# MYC_Homematic.net
KiCad netlist of a schematic drawn in EAGLE
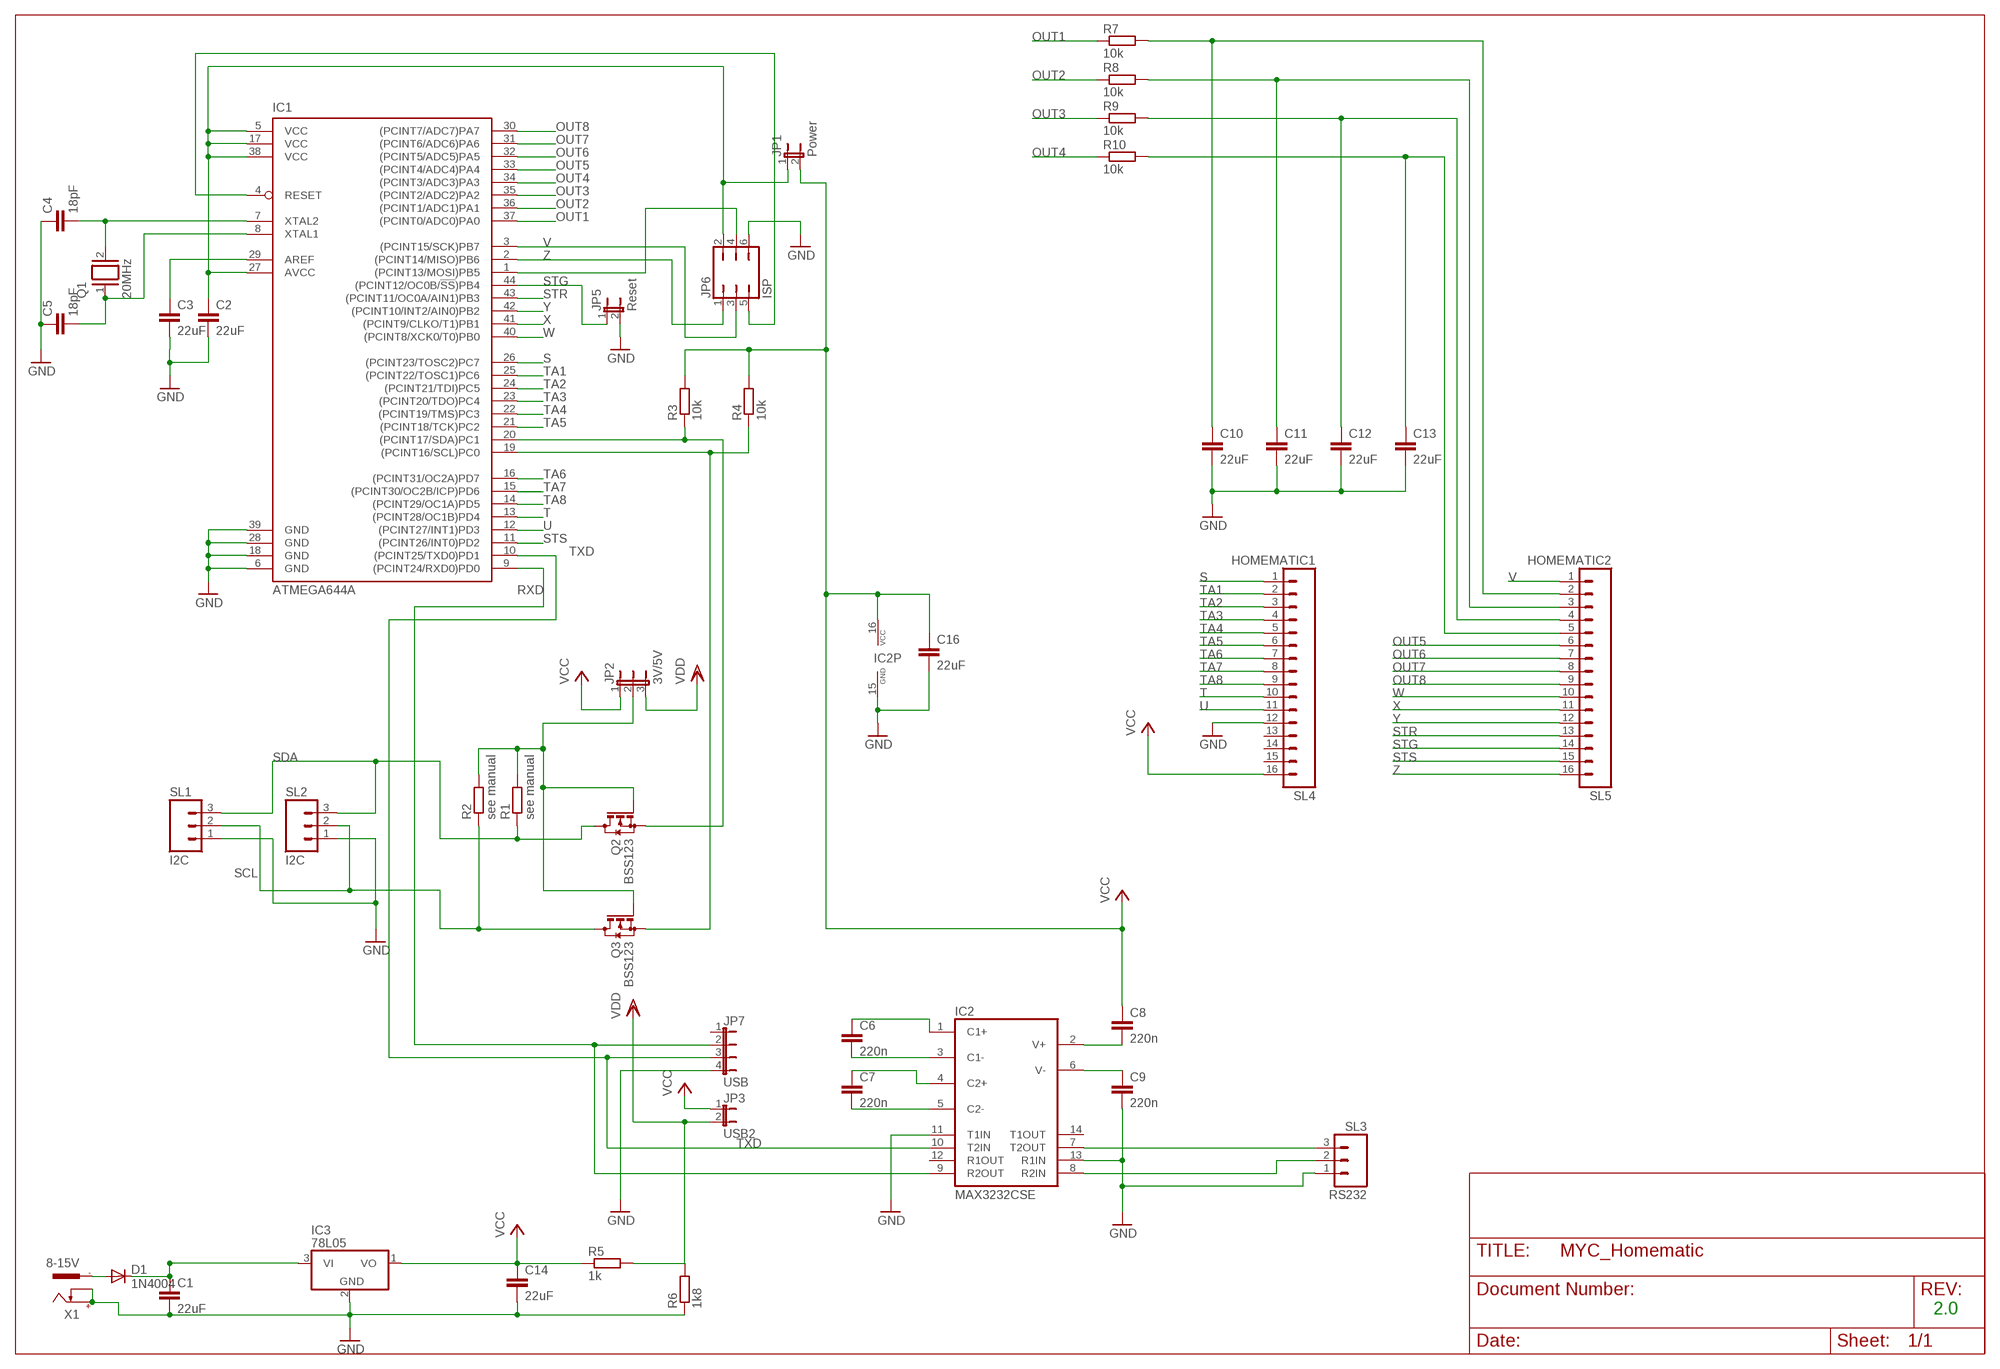
[diagram p0: schematic, sheet 1]

(export (version "E")
  (design (tool "Eeschema 10.0.6"))
  (components
    (comp (ref "C1")
      (value "22uF")
      (footprint "eagle-import:C1206")
      (libsource (lib "eagle-import") (part "C-EUC1206"))
    )
    (comp (ref "C2")
      (value "22uF")
      (footprint "eagle-import:C1206")
      (libsource (lib "eagle-import") (part "C-EUC1206"))
    )
    (comp (ref "C3")
      (value "22uF")
      (footprint "eagle-import:C1206")
      (libsource (lib "eagle-import") (part "C-EUC1206"))
    )
    (comp (ref "C4")
      (value "18pF")
      (footprint "eagle-import:C025-030X050")
      (libsource (lib "eagle-import") (part "C-EU025-030X050"))
    )
    (comp (ref "C5")
      (value "18pF")
      (footprint "eagle-import:C025-030X050")
      (libsource (lib "eagle-import") (part "C-EU025-030X050"))
    )
    (comp (ref "C6")
      (value "220n")
      (footprint "eagle-import:C1206")
      (libsource (lib "eagle-import") (part "C-EUC1206"))
    )
    (comp (ref "C7")
      (value "220n")
      (footprint "eagle-import:C1206")
      (libsource (lib "eagle-import") (part "C-EUC1206"))
    )
    (comp (ref "C8")
      (value "220n")
      (footprint "eagle-import:C1206")
      (libsource (lib "eagle-import") (part "C-EUC1206"))
    )
    (comp (ref "C9")
      (value "220n")
      (footprint "eagle-import:C1206")
      (libsource (lib "eagle-import") (part "C-EUC1206"))
    )
    (comp (ref "C10")
      (value "22uF")
      (footprint "eagle-import:C1206")
      (libsource (lib "eagle-import") (part "C-EUC1206"))
    )
    (comp (ref "C11")
      (value "22uF")
      (footprint "eagle-import:C1206")
      (libsource (lib "eagle-import") (part "C-EUC1206"))
    )
    (comp (ref "C12")
      (value "22uF")
      (footprint "eagle-import:C1206")
      (libsource (lib "eagle-import") (part "C-EUC1206"))
    )
    (comp (ref "C13")
      (value "22uF")
      (footprint "eagle-import:C1206")
      (libsource (lib "eagle-import") (part "C-EUC1206"))
    )
    (comp (ref "C14")
      (value "22uF")
      (footprint "eagle-import:C1206")
      (libsource (lib "eagle-import") (part "C-EUC1206"))
    )
    (comp (ref "C16")
      (value "22uF")
      (footprint "eagle-import:C1206")
      (libsource (lib "eagle-import") (part "C-EUC1206"))
    )
    (comp (ref "D1")
      (value "1N4004")
      (footprint "eagle-import:DO41-10")
      (libsource (lib "eagle-import") (part "1N4004"))
    )
    (comp (ref "IC1")
      (value "ATMEGA644A")
      (footprint "eagle-import:TQFP44")
      (fields (field (name "MPN") "ATMEGA644PV-10AU"))
      (libsource (lib "eagle-import") (part "ATMEGA644A"))
    )
    (comp (ref "IC2")
      (value "MAX3232CSE")
      (footprint "eagle-import:SO16")
      (libsource (lib "eagle-import") (part "MAX3232SEC"))
    )
    (comp (ref "IC3")
      (value "78L05")
      (footprint "eagle-import:TO92")
      (libsource (lib "eagle-import") (part "78L05"))
    )
    (comp (ref "JP1")
      (value "Power")
      (footprint "eagle-import:JP1")
      (libsource (lib "eagle-import") (part "JP1E"))
    )
    (comp (ref "JP2")
      (value "3V/5V")
      (footprint "eagle-import:JP2")
      (libsource (lib "eagle-import") (part "JP2E"))
    )
    (comp (ref "JP3")
      (value "USB2")
      (footprint "eagle-import:JP1")
      (libsource (lib "eagle-import") (part "JP1E"))
    )
    (comp (ref "JP5")
      (value "Reset")
      (footprint "eagle-import:JP1")
      (libsource (lib "eagle-import") (part "JP1E"))
    )
    (comp (ref "JP6")
      (value "ISP")
      (footprint "eagle-import:JP3Q")
      (libsource (lib "eagle-import") (part "JP3Q"))
    )
    (comp (ref "JP7")
      (value "USB")
      (footprint "eagle-import:JP4")
      (libsource (lib "eagle-import") (part "JP4E"))
    )
    (comp (ref "Q1")
      (value "20MHz")
      (footprint "eagle-import:QS")
      (libsource (lib "eagle-import") (part "XTAL/S"))
    )
    (comp (ref "Q2")
      (value "BSS123")
      (footprint "eagle-import:SOT23")
      (libsource (lib "eagle-import") (part "BSS123"))
    )
    (comp (ref "Q3")
      (value "BSS123")
      (footprint "eagle-import:SOT23")
      (libsource (lib "eagle-import") (part "BSS123"))
    )
    (comp (ref "R1")
      (value "see manual")
      (footprint "eagle-import:R1206")
      (libsource (lib "eagle-import") (part "R-EU_R1206"))
    )
    (comp (ref "R2")
      (value "see manual")
      (footprint "eagle-import:R1206")
      (libsource (lib "eagle-import") (part "R-EU_R1206"))
    )
    (comp (ref "R3")
      (value "10k")
      (footprint "eagle-import:R1206")
      (libsource (lib "eagle-import") (part "R-EU_R1206"))
    )
    (comp (ref "R4")
      (value "10k")
      (footprint "eagle-import:R1206")
      (libsource (lib "eagle-import") (part "R-EU_R1206"))
    )
    (comp (ref "R5")
      (value "1k")
      (footprint "eagle-import:R1206")
      (libsource (lib "eagle-import") (part "R-EU_R1206"))
    )
    (comp (ref "R6")
      (value "1k8")
      (footprint "eagle-import:R1206")
      (libsource (lib "eagle-import") (part "R-EU_R1206"))
    )
    (comp (ref "R7")
      (value "10k")
      (footprint "eagle-import:R1206")
      (libsource (lib "eagle-import") (part "R-EU_R1206"))
    )
    (comp (ref "R8")
      (value "10k")
      (footprint "eagle-import:R1206")
      (libsource (lib "eagle-import") (part "R-EU_R1206"))
    )
    (comp (ref "R9")
      (value "10k")
      (footprint "eagle-import:R1206")
      (libsource (lib "eagle-import") (part "R-EU_R1206"))
    )
    (comp (ref "R10")
      (value "10k")
      (footprint "eagle-import:R1206")
      (libsource (lib "eagle-import") (part "R-EU_R1206"))
    )
    (comp (ref "SL1")
      (value "I2C")
      (footprint "eagle-import:03P")
      (libsource (lib "eagle-import") (part "M03"))
    )
    (comp (ref "SL2")
      (value "I2C")
      (footprint "eagle-import:03P")
      (libsource (lib "eagle-import") (part "M03"))
    )
    (comp (ref "SL3")
      (value "RS232")
      (footprint "eagle-import:03P")
      (libsource (lib "eagle-import") (part "M03"))
    )
    (comp (ref "SL4")
      (value "HOMEMATIC1")
      (footprint "eagle-import:16P")
      (libsource (lib "eagle-import") (part "M16"))
    )
    (comp (ref "SL5")
      (value "HOMEMATIC2")
      (footprint "eagle-import:16P")
      (libsource (lib "eagle-import") (part "M16"))
    )
    (comp (ref "X1")
      (value "8-15V")
      (footprint "eagle-import:737992-5")
      (libsource (lib "eagle-import") (part "737992-55"))
    )
  )
  (nets
    (net (code "1") (name "/OUT1") (class "Default")
      (node (ref "IC1") (pin "37") (pinfunction "(PCINT0/ADC0)PA0_37") (pintype "bidirectional"))
      (node (ref "R7") (pin "1") (pinfunction "1_1") (pintype "passive"))
    )
    (net (code "2") (name "/OUT2") (class "Default")
      (node (ref "IC1") (pin "36") (pinfunction "(PCINT1/ADC1)PA1_36") (pintype "bidirectional"))
      (node (ref "R8") (pin "1") (pinfunction "1_1") (pintype "passive"))
    )
    (net (code "3") (name "/OUT3") (class "Default")
      (node (ref "IC1") (pin "35") (pinfunction "(PCINT2/ADC2)PA2_35") (pintype "bidirectional"))
      (node (ref "R9") (pin "1") (pinfunction "1_1") (pintype "passive"))
    )
    (net (code "4") (name "/OUT4") (class "Default")
      (node (ref "IC1") (pin "34") (pinfunction "(PCINT3/ADC3)PA3_34") (pintype "bidirectional"))
      (node (ref "R10") (pin "1") (pinfunction "1_1") (pintype "passive"))
    )
    (net (code "5") (name "/OUT5") (class "Default")
      (node (ref "IC1") (pin "33") (pinfunction "(PCINT4/ADC4)PA4_33") (pintype "bidirectional"))
      (node (ref "SL5") (pin "6") (pinfunction "6_6") (pintype "passive"))
    )
    (net (code "6") (name "/OUT6") (class "Default")
      (node (ref "IC1") (pin "32") (pinfunction "(PCINT5/ADC5)PA5_32") (pintype "bidirectional"))
      (node (ref "SL5") (pin "7") (pinfunction "7_7") (pintype "passive"))
    )
    (net (code "7") (name "/OUT7") (class "Default")
      (node (ref "IC1") (pin "31") (pinfunction "(PCINT6/ADC6)PA6_31") (pintype "bidirectional"))
      (node (ref "SL5") (pin "8") (pinfunction "8_8") (pintype "passive"))
    )
    (net (code "8") (name "/OUT8") (class "Default")
      (node (ref "IC1") (pin "30") (pinfunction "(PCINT7/ADC7)PA7_30") (pintype "bidirectional"))
      (node (ref "SL5") (pin "9") (pinfunction "9_9") (pintype "passive"))
    )
    (net (code "9") (name "/RXD") (class "Default")
      (node (ref "IC1") (pin "9") (pinfunction "(PCINT24/RXD0)PD0_9") (pintype "bidirectional"))
      (node (ref "IC2") (pin "9") (pinfunction "R2OUT_9") (pintype "output"))
      (node (ref "JP7") (pin "2") (pinfunction "2_2") (pintype "passive"))
    )
    (net (code "10") (name "/S") (class "Default")
      (node (ref "IC1") (pin "26") (pinfunction "(PCINT23/TOSC2)PC7_26") (pintype "output"))
      (node (ref "SL4") (pin "1") (pinfunction "1_1") (pintype "passive"))
    )
    (net (code "11") (name "/SCL") (class "Default")
      (node (ref "Q3") (pin "3") (pinfunction "D_3") (pintype "passive"))
      (node (ref "R2") (pin "1") (pinfunction "1_1") (pintype "passive"))
      (node (ref "SL1") (pin "2") (pinfunction "2_2") (pintype "passive"))
      (node (ref "SL2") (pin "2") (pinfunction "2_2") (pintype "passive"))
    )
    (net (code "12") (name "/SDA") (class "Default")
      (node (ref "Q2") (pin "3") (pinfunction "D_3") (pintype "passive"))
      (node (ref "R1") (pin "1") (pinfunction "1_1") (pintype "passive"))
      (node (ref "SL1") (pin "3") (pinfunction "3_3") (pintype "passive"))
      (node (ref "SL2") (pin "3") (pinfunction "3_3") (pintype "passive"))
    )
    (net (code "13") (name "/STG") (class "Default")
      (node (ref "IC1") (pin "44") (pinfunction "(PCINT12/OC0B/~{SS})PB4_44") (pintype "bidirectional"))
      (node (ref "JP5") (pin "1") (pinfunction "1_1") (pintype "passive"))
      (node (ref "SL5") (pin "14") (pinfunction "14_14") (pintype "passive"))
    )
    (net (code "14") (name "/STR") (class "Default")
      (node (ref "IC1") (pin "43") (pinfunction "(PCINT11/OC0A/AIN1)PB3_43") (pintype "bidirectional"))
      (node (ref "SL5") (pin "13") (pinfunction "13_13") (pintype "passive"))
    )
    (net (code "15") (name "/STS") (class "Default")
      (node (ref "IC1") (pin "11") (pinfunction "(PCINT26/INT0)PD2_11") (pintype "bidirectional"))
      (node (ref "SL5") (pin "15") (pinfunction "15_15") (pintype "passive"))
    )
    (net (code "16") (name "/T") (class "Default")
      (node (ref "IC1") (pin "13") (pinfunction "(PCINT28/OC1B)PD4_13") (pintype "bidirectional"))
      (node (ref "SL4") (pin "10") (pinfunction "10_10") (pintype "passive"))
    )
    (net (code "17") (name "/TA1") (class "Default")
      (node (ref "IC1") (pin "25") (pinfunction "(PCINT22/TOSC1)PC6_25") (pintype "output"))
      (node (ref "SL4") (pin "2") (pinfunction "2_2") (pintype "passive"))
    )
    (net (code "18") (name "/TA2") (class "Default")
      (node (ref "IC1") (pin "24") (pinfunction "(PCINT21/TDI)PC5_24") (pintype "output"))
      (node (ref "SL4") (pin "3") (pinfunction "3_3") (pintype "passive"))
    )
    (net (code "19") (name "/TA3") (class "Default")
      (node (ref "IC1") (pin "23") (pinfunction "(PCINT20/TDO)PC4_23") (pintype "output"))
      (node (ref "SL4") (pin "4") (pinfunction "4_4") (pintype "passive"))
    )
    (net (code "20") (name "/TA4") (class "Default")
      (node (ref "IC1") (pin "22") (pinfunction "(PCINT19/TMS)PC3_22") (pintype "output"))
      (node (ref "SL4") (pin "5") (pinfunction "5_5") (pintype "passive"))
    )
    (net (code "21") (name "/TA5") (class "Default")
      (node (ref "IC1") (pin "21") (pinfunction "(PCINT18/TCK)PC2_21") (pintype "output"))
      (node (ref "SL4") (pin "6") (pinfunction "6_6") (pintype "passive"))
    )
    (net (code "22") (name "/TA6") (class "Default")
      (node (ref "IC1") (pin "16") (pinfunction "(PCINT31/OC2A)PD7_16") (pintype "bidirectional"))
      (node (ref "SL4") (pin "7") (pinfunction "7_7") (pintype "passive"))
    )
    (net (code "23") (name "/TA7") (class "Default")
      (node (ref "IC1") (pin "15") (pinfunction "(PCINT30/OC2B/ICP)PD6_15") (pintype "bidirectional"))
      (node (ref "SL4") (pin "8") (pinfunction "8_8") (pintype "passive"))
    )
    (net (code "24") (name "/TA8") (class "Default")
      (node (ref "IC1") (pin "14") (pinfunction "(PCINT29/OC1A)PD5_14") (pintype "bidirectional"))
      (node (ref "SL4") (pin "9") (pinfunction "9_9") (pintype "passive"))
    )
    (net (code "25") (name "/TXD") (class "Default")
      (node (ref "IC1") (pin "10") (pinfunction "(PCINT25/TXD0)PD1_10") (pintype "bidirectional"))
      (node (ref "IC2") (pin "10") (pinfunction "T2IN_10") (pintype "input"))
      (node (ref "JP7") (pin "3") (pinfunction "3_3") (pintype "passive"))
    )
    (net (code "26") (name "/U") (class "Default")
      (node (ref "IC1") (pin "12") (pinfunction "(PCINT27/INT1)PD3_12") (pintype "bidirectional"))
      (node (ref "SL4") (pin "11") (pinfunction "11_11") (pintype "passive"))
    )
    (net (code "27") (name "/V") (class "Default")
      (node (ref "IC1") (pin "3") (pinfunction "(PCINT15/SCK)PB7_3") (pintype "bidirectional"))
      (node (ref "JP6") (pin "3") (pinfunction "3_3") (pintype "passive"))
      (node (ref "SL5") (pin "1") (pinfunction "1_1") (pintype "passive"))
    )
    (net (code "28") (name "/W") (class "Default")
      (node (ref "IC1") (pin "40") (pinfunction "(PCINT8/XCK0/T0)PB0_40") (pintype "bidirectional"))
      (node (ref "SL5") (pin "10") (pinfunction "10_10") (pintype "passive"))
    )
    (net (code "29") (name "/X") (class "Default")
      (node (ref "IC1") (pin "41") (pinfunction "(PCINT9/CLKO/T1)PB1_41") (pintype "bidirectional"))
      (node (ref "SL5") (pin "11") (pinfunction "11_11") (pintype "passive"))
    )
    (net (code "30") (name "/Y") (class "Default")
      (node (ref "IC1") (pin "42") (pinfunction "(PCINT10/INT2/AIN0)PB2_42") (pintype "bidirectional"))
      (node (ref "SL5") (pin "12") (pinfunction "12_12") (pintype "passive"))
    )
    (net (code "31") (name "/Z") (class "Default")
      (node (ref "IC1") (pin "2") (pinfunction "(PCINT14/MISO)PB6_2") (pintype "bidirectional"))
      (node (ref "JP6") (pin "1") (pinfunction "1_1") (pintype "passive"))
      (node (ref "SL5") (pin "16") (pinfunction "16_16") (pintype "passive"))
    )
    (net (code "32") (name "GND") (class "Default")
      (node (ref "C1") (pin "2") (pinfunction "2_2") (pintype "passive"))
      (node (ref "C10") (pin "2") (pinfunction "2_2") (pintype "passive"))
      (node (ref "C11") (pin "2") (pinfunction "2_2") (pintype "passive"))
      (node (ref "C12") (pin "2") (pinfunction "2_2") (pintype "passive"))
      (node (ref "C13") (pin "2") (pinfunction "2_2") (pintype "passive"))
      (node (ref "C14") (pin "2") (pinfunction "2_2") (pintype "passive"))
      (node (ref "C16") (pin "2") (pinfunction "2_2") (pintype "passive"))
      (node (ref "C2") (pin "2") (pinfunction "2_2") (pintype "passive"))
      (node (ref "C3") (pin "2") (pinfunction "2_2") (pintype "passive"))
      (node (ref "C4") (pin "1") (pinfunction "1_1") (pintype "passive"))
      (node (ref "C5") (pin "1") (pinfunction "1_1") (pintype "passive"))
      (node (ref "C9") (pin "2") (pinfunction "2_2") (pintype "passive"))
      (node (ref "IC1") (pin "18") (pinfunction "GND_18") (pintype "power_in"))
      (node (ref "IC1") (pin "28") (pinfunction "GND_28") (pintype "power_in"))
      (node (ref "IC1") (pin "39") (pinfunction "GND_39") (pintype "power_in"))
      (node (ref "IC1") (pin "6") (pinfunction "GND_6") (pintype "power_in"))
      (node (ref "IC2") (pin "11") (pinfunction "T1IN_11") (pintype "input"))
      (node (ref "IC2") (pin "13") (pinfunction "R1IN_13") (pintype "input"))
      (node (ref "IC2") (pin "15") (pinfunction "GND_15") (pintype "power_in"))
      (node (ref "IC3") (pin "2") (pinfunction "GND_2") (pintype "passive"))
      (node (ref "JP5") (pin "2") (pinfunction "2_2") (pintype "passive"))
      (node (ref "JP6") (pin "6") (pinfunction "6_6") (pintype "passive"))
      (node (ref "JP7") (pin "4") (pinfunction "4_4") (pintype "passive"))
      (node (ref "R6") (pin "1") (pinfunction "1_1") (pintype "passive"))
      (node (ref "SL1") (pin "1") (pinfunction "1_1") (pintype "passive"))
      (node (ref "SL2") (pin "1") (pinfunction "1_1") (pintype "passive"))
      (node (ref "SL3") (pin "1") (pinfunction "1_1") (pintype "passive"))
      (node (ref "SL4") (pin "12") (pinfunction "12_12") (pintype "passive"))
      (node (ref "X1") (pin "+") (pinfunction "+_+") (pintype "passive"))
      (node (ref "X1") (pin "K") (pinfunction "K_K") (pintype "passive"))
    )
    (net (code "33") (name "Net-(C10-Pad1)") (class "Default")
      (node (ref "C10") (pin "1") (pinfunction "1_1") (pintype "passive"))
      (node (ref "R7") (pin "2") (pinfunction "2_2") (pintype "passive"))
      (node (ref "SL5") (pin "2") (pinfunction "2_2") (pintype "passive"))
    )
    (net (code "34") (name "Net-(C11-Pad1)") (class "Default")
      (node (ref "C11") (pin "1") (pinfunction "1_1") (pintype "passive"))
      (node (ref "R8") (pin "2") (pinfunction "2_2") (pintype "passive"))
      (node (ref "SL5") (pin "3") (pinfunction "3_3") (pintype "passive"))
    )
    (net (code "35") (name "Net-(C12-Pad1)") (class "Default")
      (node (ref "C12") (pin "1") (pinfunction "1_1") (pintype "passive"))
      (node (ref "R9") (pin "2") (pinfunction "2_2") (pintype "passive"))
      (node (ref "SL5") (pin "4") (pinfunction "4_4") (pintype "passive"))
    )
    (net (code "36") (name "Net-(C13-Pad1)") (class "Default")
      (node (ref "C13") (pin "1") (pinfunction "1_1") (pintype "passive"))
      (node (ref "R10") (pin "2") (pinfunction "2_2") (pintype "passive"))
      (node (ref "SL5") (pin "5") (pinfunction "5_5") (pintype "passive"))
    )
    (net (code "37") (name "Net-(D1-PadA)") (class "Default")
      (node (ref "D1") (pin "A") (pinfunction "A_A") (pintype "passive"))
      (node (ref "X1") (pin "-1") (pinfunction "-1_-1") (pintype "passive"))
    )
    (net (code "38") (name "Net-(IC1-(PCINT13{slash}MOSI)PB5)") (class "Default")
      (node (ref "IC1") (pin "1") (pinfunction "(PCINT13/MOSI)PB5_1") (pintype "bidirectional"))
      (node (ref "JP6") (pin "4") (pinfunction "4_4") (pintype "passive"))
    )
    (net (code "39") (name "Net-(IC1-(PCINT16{slash}SCL)PC0)") (class "Default")
      (node (ref "IC1") (pin "19") (pinfunction "(PCINT16/SCL)PC0_19") (pintype "output"))
      (node (ref "Q3") (pin "2") (pinfunction "S_2") (pintype "passive"))
      (node (ref "R4") (pin "1") (pinfunction "1_1") (pintype "passive"))
    )
    (net (code "40") (name "Net-(IC1-(PCINT17{slash}SDA)PC1)") (class "Default")
      (node (ref "IC1") (pin "20") (pinfunction "(PCINT17/SDA)PC1_20") (pintype "output"))
      (node (ref "Q2") (pin "2") (pinfunction "S_2") (pintype "passive"))
      (node (ref "R3") (pin "1") (pinfunction "1_1") (pintype "passive"))
    )
    (net (code "41") (name "Net-(IC1-AREF)") (class "Default")
      (node (ref "C3") (pin "1") (pinfunction "1_1") (pintype "passive"))
      (node (ref "IC1") (pin "29") (pinfunction "AREF_29") (pintype "passive"))
    )
    (net (code "42") (name "Net-(IC1-AVCC)") (class "Default")
      (node (ref "C2") (pin "1") (pinfunction "1_1") (pintype "passive"))
      (node (ref "IC1") (pin "17") (pinfunction "VCC_17") (pintype "power_in"))
      (node (ref "IC1") (pin "27") (pinfunction "AVCC_27") (pintype "power_in"))
      (node (ref "IC1") (pin "38") (pinfunction "VCC_38") (pintype "power_in"))
      (node (ref "IC1") (pin "5") (pinfunction "VCC_5") (pintype "power_in"))
      (node (ref "JP1") (pin "1") (pinfunction "1_1") (pintype "passive"))
      (node (ref "JP6") (pin "2") (pinfunction "2_2") (pintype "passive"))
    )
    (net (code "43") (name "Net-(IC1-RESET)") (class "Default")
      (node (ref "IC1") (pin "4") (pinfunction "RESET_4") (pintype "input"))
      (node (ref "JP6") (pin "5") (pinfunction "5_5") (pintype "passive"))
    )
    (net (code "44") (name "Net-(IC1-XTAL1)") (class "Default")
      (node (ref "C5") (pin "2") (pinfunction "2_2") (pintype "passive"))
      (node (ref "IC1") (pin "8") (pinfunction "XTAL1_8") (pintype "bidirectional"))
      (node (ref "Q1") (pin "1") (pinfunction "1_1") (pintype "passive"))
    )
    (net (code "45") (name "Net-(IC1-XTAL2)") (class "Default")
      (node (ref "C4") (pin "2") (pinfunction "2_2") (pintype "passive"))
      (node (ref "IC1") (pin "7") (pinfunction "XTAL2_7") (pintype "bidirectional"))
      (node (ref "Q1") (pin "2") (pinfunction "2_2") (pintype "passive"))
    )
    (net (code "46") (name "Net-(IC2A-C1+)") (class "Default")
      (node (ref "C6") (pin "1") (pinfunction "1_1") (pintype "passive"))
      (node (ref "IC2") (pin "1") (pinfunction "C1+_1") (pintype "bidirectional"))
    )
    (net (code "47") (name "Net-(IC2A-C1-)") (class "Default")
      (node (ref "C6") (pin "2") (pinfunction "2_2") (pintype "passive"))
      (node (ref "IC2") (pin "3") (pinfunction "C1-_3") (pintype "bidirectional"))
    )
    (net (code "48") (name "Net-(IC2A-C2+)") (class "Default")
      (node (ref "C7") (pin "1") (pinfunction "1_1") (pintype "passive"))
      (node (ref "IC2") (pin "4") (pinfunction "C2+_4") (pintype "bidirectional"))
    )
    (net (code "49") (name "Net-(IC2A-C2-)") (class "Default")
      (node (ref "C7") (pin "2") (pinfunction "2_2") (pintype "passive"))
      (node (ref "IC2") (pin "5") (pinfunction "C2-_5") (pintype "bidirectional"))
    )
    (net (code "50") (name "Net-(IC2A-R2IN)") (class "Default")
      (node (ref "IC2") (pin "8") (pinfunction "R2IN_8") (pintype "input"))
      (node (ref "SL3") (pin "2") (pinfunction "2_2") (pintype "passive"))
    )
    (net (code "51") (name "Net-(IC2A-T2OUT)") (class "Default")
      (node (ref "IC2") (pin "7") (pinfunction "T2OUT_7") (pintype "output"))
      (node (ref "SL3") (pin "3") (pinfunction "3_3") (pintype "passive"))
    )
    (net (code "52") (name "Net-(IC2A-V+)") (class "Default")
      (node (ref "C8") (pin "2") (pinfunction "2_2") (pintype "passive"))
      (node (ref "IC2") (pin "2") (pinfunction "V+_2") (pintype "bidirectional"))
    )
    (net (code "53") (name "Net-(IC2A-V-)") (class "Default")
      (node (ref "C9") (pin "1") (pinfunction "1_1") (pintype "passive"))
      (node (ref "IC2") (pin "6") (pinfunction "V-_6") (pintype "bidirectional"))
    )
    (net (code "54") (name "Net-(IC3-VI)") (class "Default")
      (node (ref "C1") (pin "1") (pinfunction "1_1") (pintype "passive"))
      (node (ref "D1") (pin "C") (pinfunction "C_C") (pintype "passive"))
      (node (ref "IC3") (pin "3") (pinfunction "VI_3") (pintype "input"))
    )
    (net (code "55") (name "Net-(Q2-G)") (class "Default")
      (node (ref "JP2") (pin "2") (pinfunction "2_2") (pintype "passive"))
      (node (ref "Q2") (pin "1") (pinfunction "G_1") (pintype "passive"))
      (node (ref "Q3") (pin "1") (pinfunction "G_1") (pintype "passive"))
      (node (ref "R1") (pin "2") (pinfunction "2_2") (pintype "passive"))
      (node (ref "R2") (pin "2") (pinfunction "2_2") (pintype "passive"))
    )
    (net (code "56") (name "VCC") (class "Default")
      (node (ref "C14") (pin "1") (pinfunction "1_1") (pintype "passive"))
      (node (ref "C16") (pin "1") (pinfunction "1_1") (pintype "passive"))
      (node (ref "C8") (pin "1") (pinfunction "1_1") (pintype "passive"))
      (node (ref "IC2") (pin "16") (pinfunction "VCC_16") (pintype "power_in"))
      (node (ref "IC3") (pin "1") (pinfunction "VO_1") (pintype "passive"))
      (node (ref "JP1") (pin "2") (pinfunction "2_2") (pintype "passive"))
      (node (ref "JP2") (pin "1") (pinfunction "1_1") (pintype "passive"))
      (node (ref "JP3") (pin "1") (pinfunction "1_1") (pintype "passive"))
      (node (ref "R3") (pin "2") (pinfunction "2_2") (pintype "passive"))
      (node (ref "R4") (pin "2") (pinfunction "2_2") (pintype "passive"))
      (node (ref "R5") (pin "1") (pinfunction "1_1") (pintype "passive"))
      (node (ref "SL4") (pin "16") (pinfunction "16_16") (pintype "passive"))
    )
    (net (code "57") (name "VDD") (class "Default")
      (node (ref "JP2") (pin "3") (pinfunction "3_3") (pintype "passive"))
      (node (ref "JP3") (pin "2") (pinfunction "2_2") (pintype "passive"))
      (node (ref "R5") (pin "2") (pinfunction "2_2") (pintype "passive"))
      (node (ref "R6") (pin "2") (pinfunction "2_2") (pintype "passive"))
    )
    (net (code "58") (name "unconnected-(IC2A-R1OUT-Pad12)") (class "Default")
      (node (ref "IC2") (pin "12") (pinfunction "R1OUT_12") (pintype "output"))
    )
    (net (code "59") (name "unconnected-(IC2A-T1OUT-Pad14)") (class "Default")
      (node (ref "IC2") (pin "14") (pinfunction "T1OUT_14") (pintype "output"))
    )
    (net (code "60") (name "unconnected-(JP7-Pad1)") (class "Default")
      (node (ref "JP7") (pin "1") (pinfunction "1_1") (pintype "passive"))
    )
    (net (code "61") (name "unconnected-(SL4-Pad13)") (class "Default")
      (node (ref "SL4") (pin "13") (pinfunction "13_13") (pintype "passive"))
    )
    (net (code "62") (name "unconnected-(SL4-Pad14)") (class "Default")
      (node (ref "SL4") (pin "14") (pinfunction "14_14") (pintype "passive"))
    )
    (net (code "63") (name "unconnected-(SL4-Pad15)") (class "Default")
      (node (ref "SL4") (pin "15") (pinfunction "15_15") (pintype "passive"))
    )
    (net (code "64") (name "unconnected-(X1-Pad-2)") (class "Default")
      (node (ref "X1") (pin "-2") (pinfunction "-2_-2") (pintype "passive"))
    )
  )
)
